# ItsyBitsy_Keybow_04.net
KiCad netlist of a schematic drawn in EAGLE
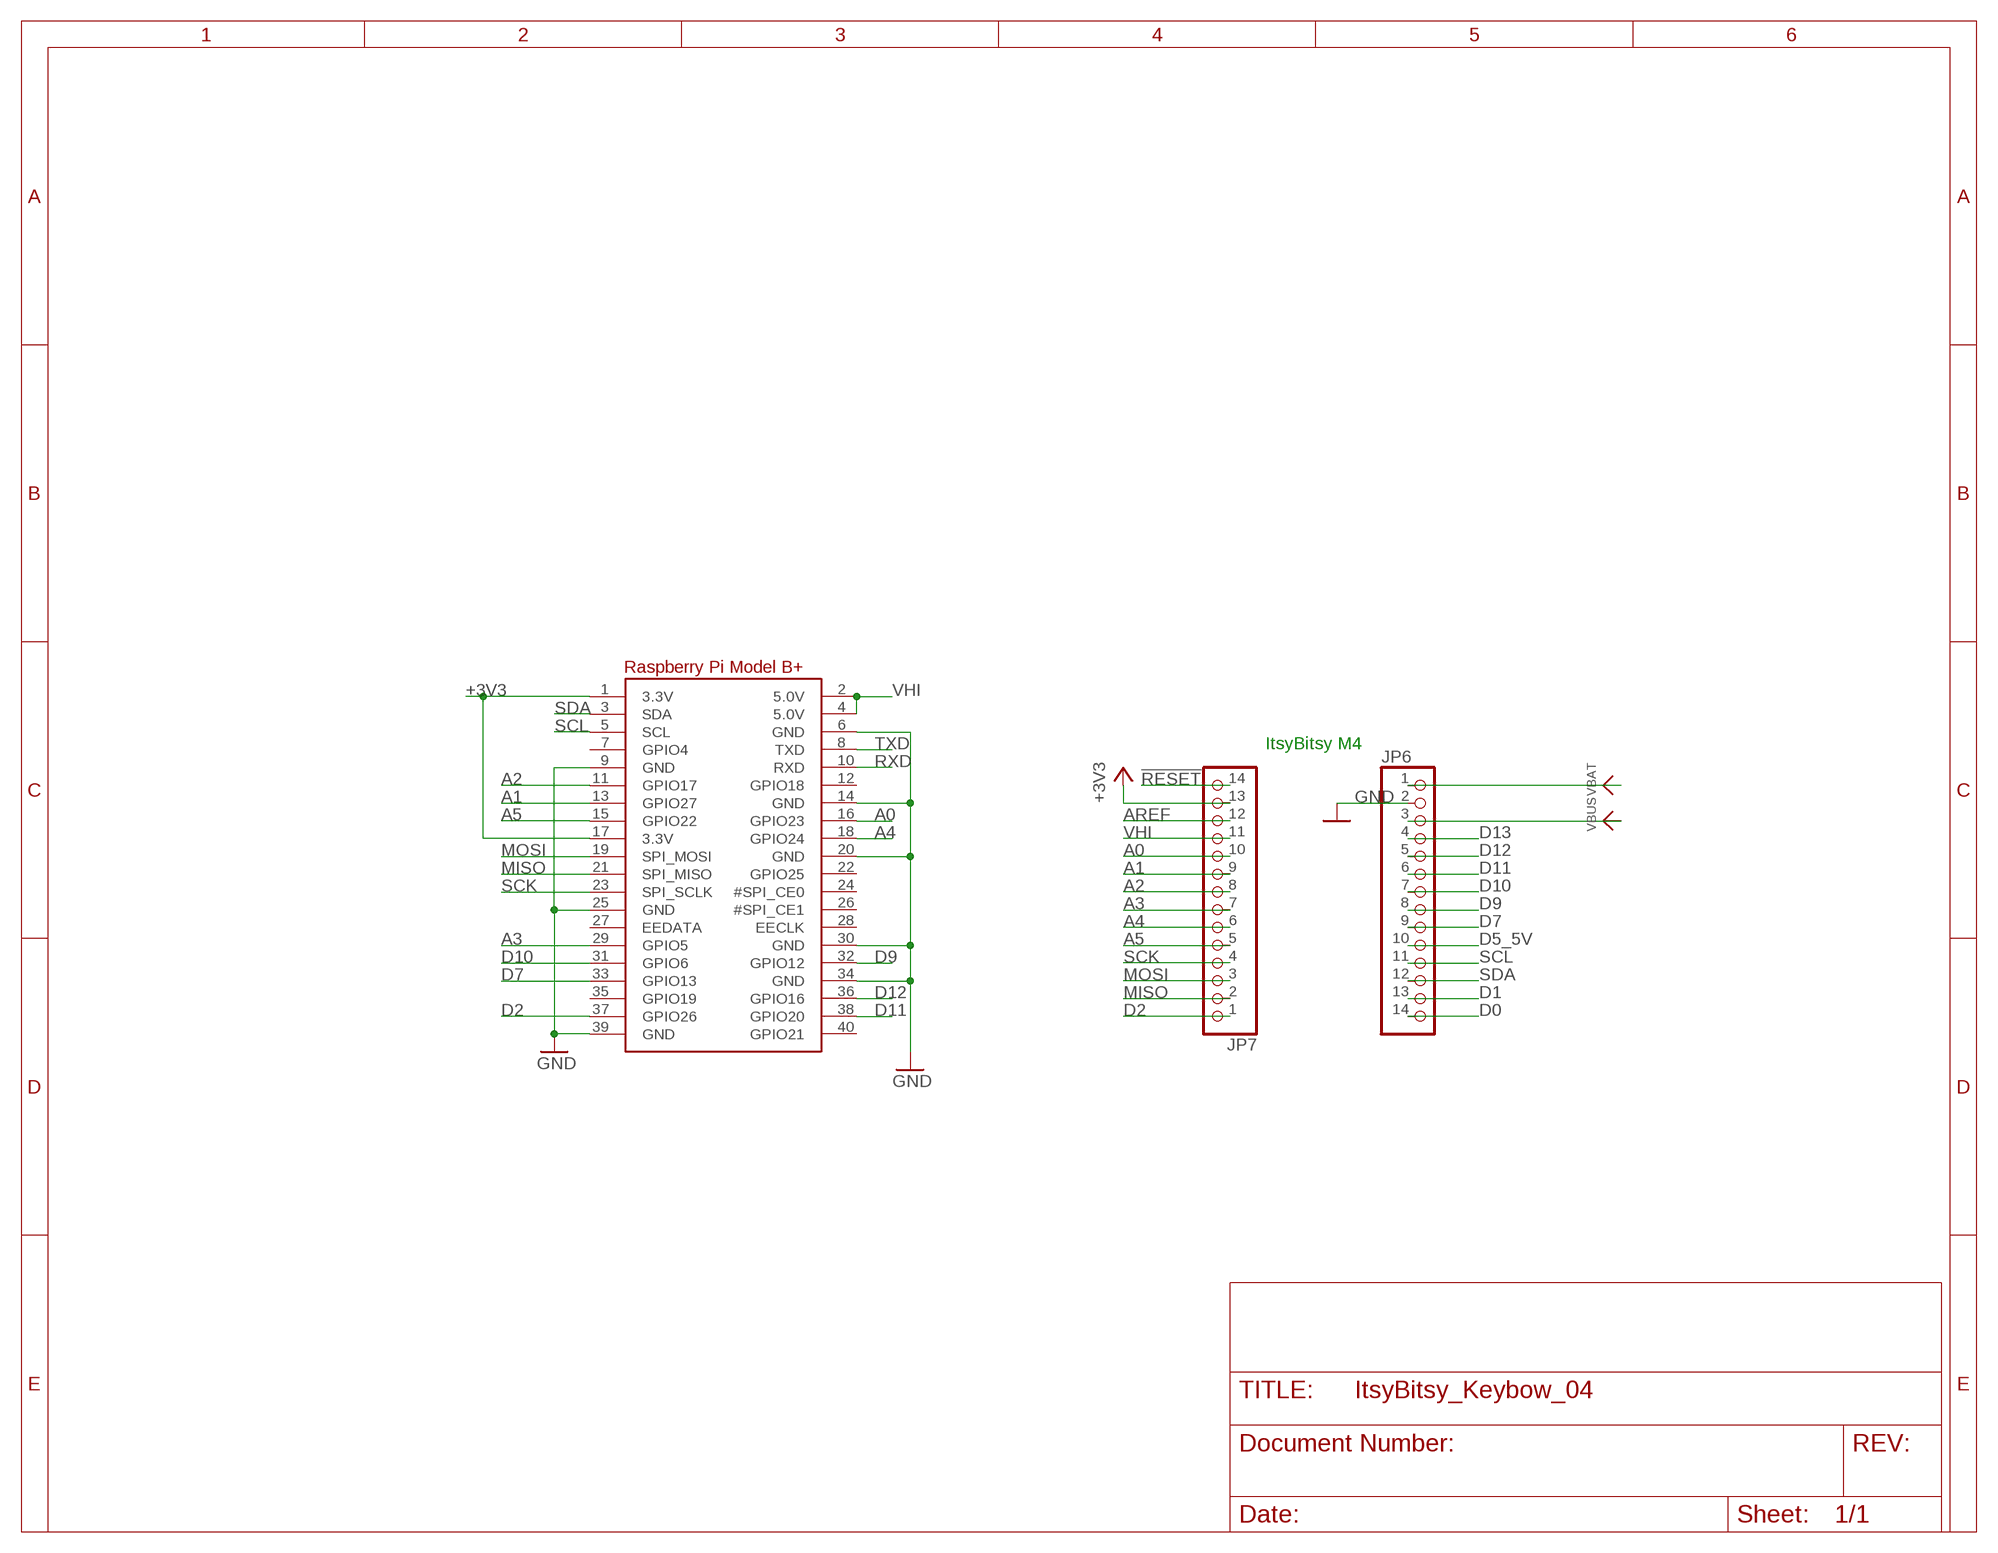
[diagram p0: schematic, sheet 1]

(export (version "E")
  (design (tool "Eeschema 10.0.6"))
  (components
    (comp (ref "JP6")
      (value "HEADER-1X14")
      (footprint "eagle-import:1X14_ROUND70")
      (libsource (lib "eagle-import") (part "HEADER-1X14"))
    )
    (comp (ref "JP7")
      (value "HEADER-1X14")
      (footprint "eagle-import:1X14_ROUND70")
      (libsource (lib "eagle-import") (part "HEADER-1X14"))
    )
    (comp (ref "RPI1")
      (value "RASPBERRYPI_BPLUS_BONNETNODIM")
      (footprint "eagle-import:PI_BONNET_NODIM")
      (libsource (lib "eagle-import") (part "RASPBERRYPI_BPLUS_BONNETNODIM"))
    )
  )
  (nets
    (net (code "1") (name "+3V3") (class "Default")
      (node (ref "JP7") (pin "13") (pinfunction "13_13") (pintype "passive"))
      (node (ref "RPI1") (pin "1") (pinfunction "3.3V_1") (pintype "power_in"))
      (node (ref "RPI1") (pin "17") (pinfunction "3.3V_17") (pintype "power_in"))
    )
    (net (code "2") (name "/A0") (class "Default")
      (node (ref "JP7") (pin "10") (pinfunction "10_10") (pintype "passive"))
      (node (ref "RPI1") (pin "16") (pinfunction "GPIO23_16") (pintype "bidirectional"))
    )
    (net (code "3") (name "/A1") (class "Default")
      (node (ref "JP7") (pin "9") (pinfunction "9_9") (pintype "passive"))
      (node (ref "RPI1") (pin "13") (pinfunction "GPIO27_13") (pintype "bidirectional"))
    )
    (net (code "4") (name "/A2") (class "Default")
      (node (ref "JP7") (pin "8") (pinfunction "8_8") (pintype "passive"))
      (node (ref "RPI1") (pin "11") (pinfunction "GPIO17_11") (pintype "bidirectional"))
    )
    (net (code "5") (name "/A3") (class "Default")
      (node (ref "JP7") (pin "7") (pinfunction "7_7") (pintype "passive"))
      (node (ref "RPI1") (pin "29") (pinfunction "GPIO5_29") (pintype "bidirectional"))
    )
    (net (code "6") (name "/A4") (class "Default")
      (node (ref "JP7") (pin "6") (pinfunction "6_6") (pintype "passive"))
      (node (ref "RPI1") (pin "18") (pinfunction "GPIO24_18") (pintype "bidirectional"))
    )
    (net (code "7") (name "/A5") (class "Default")
      (node (ref "JP7") (pin "5") (pinfunction "5_5") (pintype "passive"))
      (node (ref "RPI1") (pin "15") (pinfunction "GPIO22_15") (pintype "bidirectional"))
    )
    (net (code "8") (name "/AREF") (class "Default")
      (node (ref "JP7") (pin "12") (pinfunction "12_12") (pintype "passive"))
    )
    (net (code "9") (name "/D0") (class "Default")
      (node (ref "JP6") (pin "14") (pinfunction "14_14") (pintype "passive"))
    )
    (net (code "10") (name "/D1") (class "Default")
      (node (ref "JP6") (pin "13") (pinfunction "13_13") (pintype "passive"))
    )
    (net (code "11") (name "/D2") (class "Default")
      (node (ref "JP7") (pin "1") (pinfunction "1_1") (pintype "passive"))
      (node (ref "RPI1") (pin "37") (pinfunction "GPIO26_37") (pintype "bidirectional"))
    )
    (net (code "12") (name "/D5_5V") (class "Default")
      (node (ref "JP6") (pin "10") (pinfunction "10_10") (pintype "passive"))
    )
    (net (code "13") (name "/D7") (class "Default")
      (node (ref "JP6") (pin "9") (pinfunction "9_9") (pintype "passive"))
      (node (ref "RPI1") (pin "33") (pinfunction "GPIO13_33") (pintype "bidirectional"))
    )
    (net (code "14") (name "/D9") (class "Default")
      (node (ref "JP6") (pin "8") (pinfunction "8_8") (pintype "passive"))
      (node (ref "RPI1") (pin "32") (pinfunction "GPIO12_32") (pintype "bidirectional"))
    )
    (net (code "15") (name "/D10") (class "Default")
      (node (ref "JP6") (pin "7") (pinfunction "7_7") (pintype "passive"))
      (node (ref "RPI1") (pin "31") (pinfunction "GPIO6_31") (pintype "bidirectional"))
    )
    (net (code "16") (name "/D11") (class "Default")
      (node (ref "JP6") (pin "6") (pinfunction "6_6") (pintype "passive"))
      (node (ref "RPI1") (pin "38") (pinfunction "GPIO20_38") (pintype "bidirectional"))
    )
    (net (code "17") (name "/D12") (class "Default")
      (node (ref "JP6") (pin "5") (pinfunction "5_5") (pintype "passive"))
      (node (ref "RPI1") (pin "36") (pinfunction "GPIO16_36") (pintype "bidirectional"))
    )
    (net (code "18") (name "/D13") (class "Default")
      (node (ref "JP6") (pin "4") (pinfunction "4_4") (pintype "passive"))
    )
    (net (code "19") (name "/MISO") (class "Default")
      (node (ref "JP7") (pin "2") (pinfunction "2_2") (pintype "passive"))
      (node (ref "RPI1") (pin "21") (pinfunction "SPI_MISO_21") (pintype "bidirectional"))
    )
    (net (code "20") (name "/MOSI") (class "Default")
      (node (ref "JP7") (pin "3") (pinfunction "3_3") (pintype "passive"))
      (node (ref "RPI1") (pin "19") (pinfunction "SPI_MOSI_19") (pintype "bidirectional"))
    )
    (net (code "21") (name "/RXD") (class "Default")
      (node (ref "RPI1") (pin "10") (pinfunction "RXD_10") (pintype "bidirectional"))
    )
    (net (code "22") (name "/SCK") (class "Default")
      (node (ref "JP7") (pin "4") (pinfunction "4_4") (pintype "passive"))
      (node (ref "RPI1") (pin "23") (pinfunction "SPI_SCLK_23") (pintype "bidirectional"))
    )
    (net (code "23") (name "/SCL") (class "Default")
      (node (ref "JP6") (pin "11") (pinfunction "11_11") (pintype "passive"))
      (node (ref "RPI1") (pin "5") (pinfunction "SCL_5") (pintype "bidirectional"))
    )
    (net (code "24") (name "/SDA") (class "Default")
      (node (ref "JP6") (pin "12") (pinfunction "12_12") (pintype "passive"))
      (node (ref "RPI1") (pin "3") (pinfunction "SDA_3") (pintype "bidirectional"))
    )
    (net (code "25") (name "/TXD") (class "Default")
      (node (ref "RPI1") (pin "8") (pinfunction "TXD_8") (pintype "bidirectional"))
    )
    (net (code "26") (name "/VHI") (class "Default")
      (node (ref "JP7") (pin "11") (pinfunction "11_11") (pintype "passive"))
      (node (ref "RPI1") (pin "2") (pinfunction "5.0V_2") (pintype "power_in"))
      (node (ref "RPI1") (pin "4") (pinfunction "5.0V_4") (pintype "power_in"))
    )
    (net (code "27") (name "/~{RESET}") (class "Default")
      (node (ref "JP7") (pin "14") (pinfunction "14_14") (pintype "passive"))
    )
    (net (code "28") (name "GND") (class "Default")
      (node (ref "JP6") (pin "2") (pinfunction "2_2") (pintype "passive"))
      (node (ref "RPI1") (pin "14") (pinfunction "GND_14") (pintype "power_in"))
      (node (ref "RPI1") (pin "20") (pinfunction "GND_20") (pintype "power_in"))
      (node (ref "RPI1") (pin "25") (pinfunction "GND_25") (pintype "power_in"))
      (node (ref "RPI1") (pin "30") (pinfunction "GND_30") (pintype "power_in"))
      (node (ref "RPI1") (pin "34") (pinfunction "GND_34") (pintype "power_in"))
      (node (ref "RPI1") (pin "39") (pinfunction "GND_39") (pintype "power_in"))
      (node (ref "RPI1") (pin "6") (pinfunction "GND_6") (pintype "power_in"))
      (node (ref "RPI1") (pin "9") (pinfunction "GND_9") (pintype "power_in"))
    )
    (net (code "29") (name "VBAT") (class "Default")
      (node (ref "JP6") (pin "1") (pinfunction "1_1") (pintype "passive"))
    )
    (net (code "30") (name "VBUS") (class "Default")
      (node (ref "JP6") (pin "3") (pinfunction "3_3") (pintype "passive"))
    )
    (net (code "31") (name "unconnected-(RPI1-#SPI_CE0-Pad24)") (class "Default")
      (node (ref "RPI1") (pin "24") (pinfunction "#SPI_CE0_24") (pintype "bidirectional"))
    )
    (net (code "32") (name "unconnected-(RPI1-#SPI_CE1-Pad26)") (class "Default")
      (node (ref "RPI1") (pin "26") (pinfunction "#SPI_CE1_26") (pintype "bidirectional"))
    )
    (net (code "33") (name "unconnected-(RPI1-EECLK-Pad28)") (class "Default")
      (node (ref "RPI1") (pin "28") (pinfunction "EECLK_28") (pintype "bidirectional"))
    )
    (net (code "34") (name "unconnected-(RPI1-EEDATA-Pad27)") (class "Default")
      (node (ref "RPI1") (pin "27") (pinfunction "EEDATA_27") (pintype "bidirectional"))
    )
    (net (code "35") (name "unconnected-(RPI1-GPIO4-Pad7)") (class "Default")
      (node (ref "RPI1") (pin "7") (pinfunction "GPIO4_7") (pintype "bidirectional"))
    )
    (net (code "36") (name "unconnected-(RPI1-GPIO18-Pad12)") (class "Default")
      (node (ref "RPI1") (pin "12") (pinfunction "GPIO18_12") (pintype "bidirectional"))
    )
    (net (code "37") (name "unconnected-(RPI1-GPIO19-Pad35)") (class "Default")
      (node (ref "RPI1") (pin "35") (pinfunction "GPIO19_35") (pintype "bidirectional"))
    )
    (net (code "38") (name "unconnected-(RPI1-GPIO21-Pad40)") (class "Default")
      (node (ref "RPI1") (pin "40") (pinfunction "GPIO21_40") (pintype "bidirectional"))
    )
    (net (code "39") (name "unconnected-(RPI1-GPIO25-Pad22)") (class "Default")
      (node (ref "RPI1") (pin "22") (pinfunction "GPIO25_22") (pintype "bidirectional"))
    )
  )
)
